# Foc_Power.net
KiCad netlist of a schematic drawn in Altium Designer
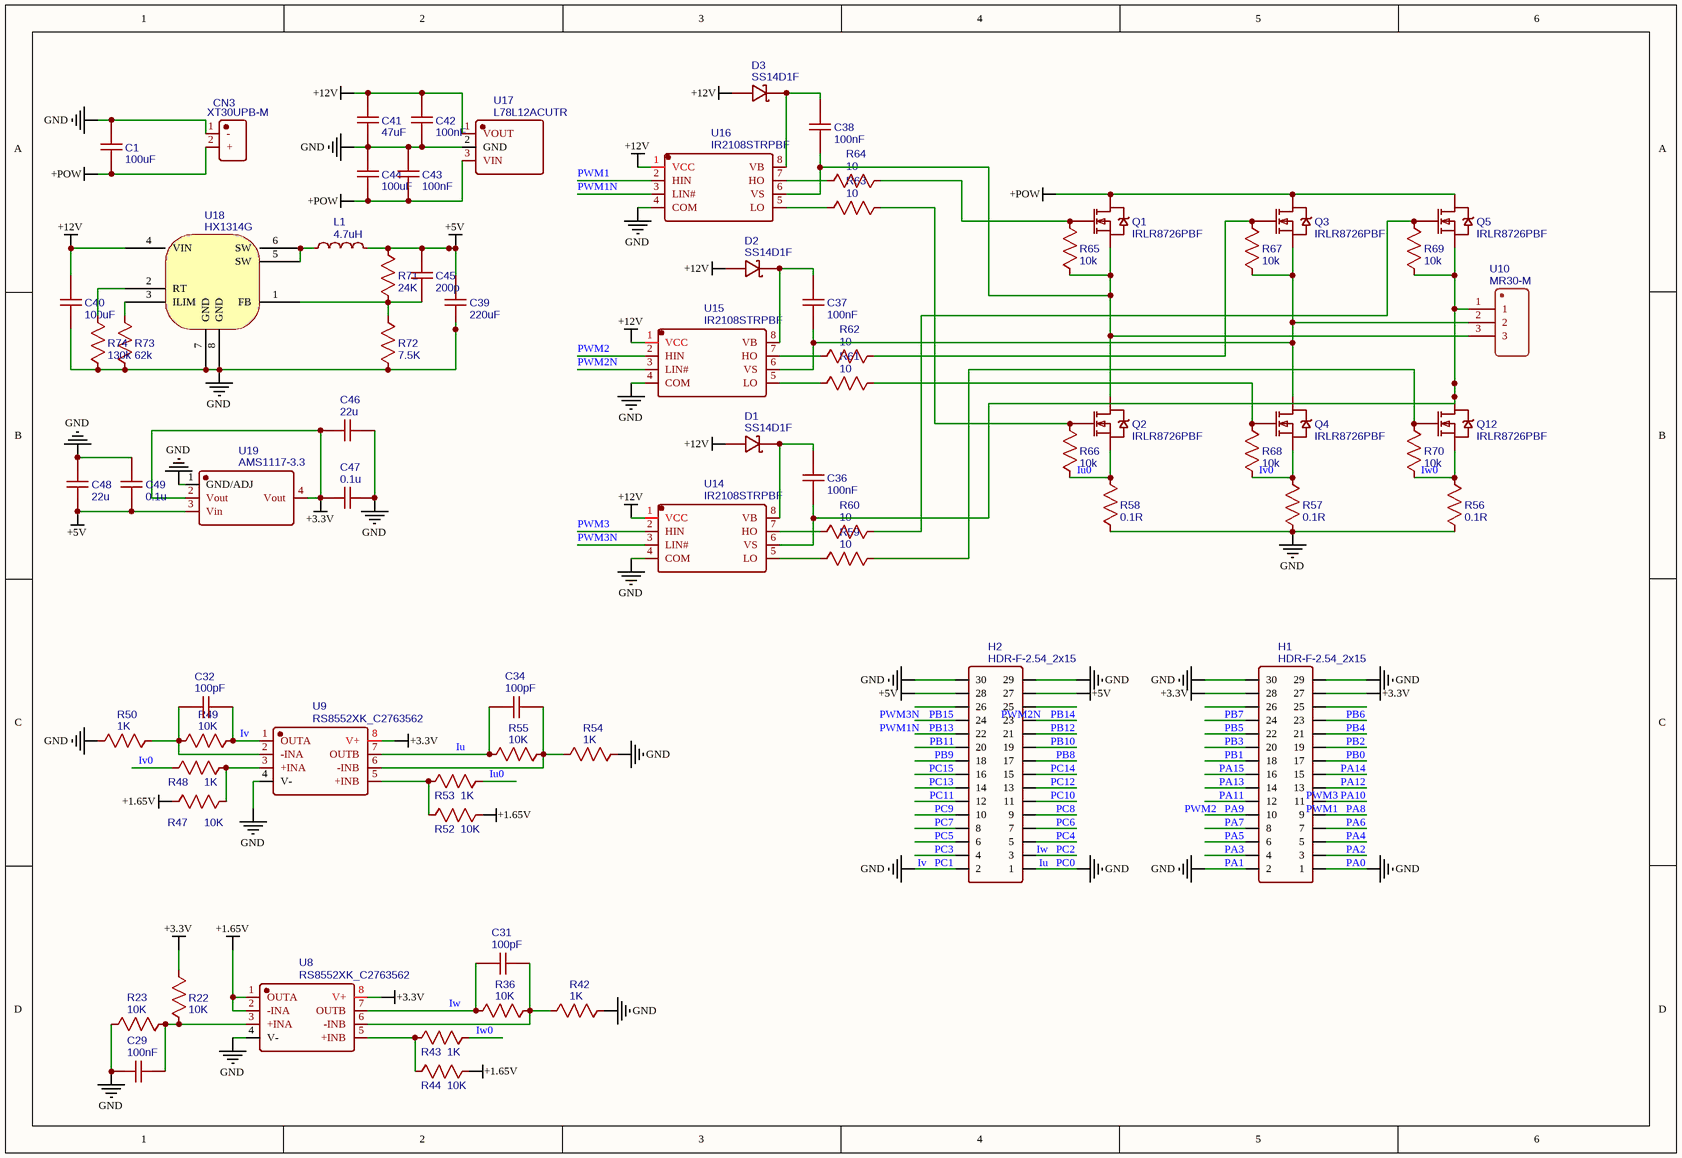
[diagram p0: Foc_Power.schdoc]

(export (version "E")
  (design (tool "Eeschema 10.0.6"))
  (components
    (comp (ref "C1")
      (value "100uF")
      (footprint "C1206")
      (fields (field (name "CONTRIBUTOR") "LCEDA_Lib"))
      (libsource (lib "altium-import") (part "root_1_100uF_"))
    )
    (comp (ref "C29")
      (value "100nF")
      (footprint "C0603")
      (fields (field (name "CONTRIBUTOR") "LCEDA_Lib"))
      (libsource (lib "altium-import") (part "root_2_100nF_"))
    )
    (comp (ref "C31")
      (value "100pF")
      (footprint "C0603")
      (fields (field (name "CONTRIBUTOR") "LCEDA_Lib"))
      (libsource (lib "altium-import") (part "root_2_100pF_"))
    )
    (comp (ref "C32")
      (value "100pF")
      (footprint "C0603")
      (fields (field (name "CONTRIBUTOR") "LCEDA_Lib"))
      (libsource (lib "altium-import") (part "root_2_100pF_"))
    )
    (comp (ref "C34")
      (value "100pF")
      (footprint "C0603")
      (fields (field (name "CONTRIBUTOR") "LCEDA_Lib"))
      (libsource (lib "altium-import") (part "root_2_100pF_"))
    )
    (comp (ref "C36")
      (value "100nF")
      (footprint "C0603")
      (fields (field (name "CONTRIBUTOR") "LCEDA_Lib"))
      (libsource (lib "altium-import") (part "root_1_100nF_"))
    )
    (comp (ref "C37")
      (value "100nF")
      (footprint "C0603")
      (fields (field (name "CONTRIBUTOR") "LCEDA_Lib"))
      (libsource (lib "altium-import") (part "root_1_100nF_"))
    )
    (comp (ref "C38")
      (value "100nF")
      (footprint "C0603")
      (fields (field (name "CONTRIBUTOR") "LCEDA_Lib"))
      (libsource (lib "altium-import") (part "root_1_100nF_"))
    )
    (comp (ref "C39")
      (value "220uF")
      (footprint "C1206")
      (fields (field (name "CONTRIBUTOR") "LCEDA_Lib"))
      (libsource (lib "altium-import") (part "root_1_220uF_"))
    )
    (comp (ref "C40")
      (value "100uF")
      (footprint "C1206")
      (fields (field (name "CONTRIBUTOR") "LCEDA_Lib"))
      (libsource (lib "altium-import") (part "root_1_100uF_"))
    )
    (comp (ref "C41")
      (value "47uF")
      (footprint "C1206")
      (fields (field (name "CONTRIBUTOR") "LCEDA_Lib"))
      (libsource (lib "altium-import") (part "root_1_47uF_"))
    )
    (comp (ref "C42")
      (value "100nF")
      (footprint "C1206")
      (fields (field (name "CONTRIBUTOR") "LCEDA_Lib"))
      (libsource (lib "altium-import") (part "root_1_100nF_"))
    )
    (comp (ref "C43")
      (value "100nF")
      (footprint "C1206")
      (fields (field (name "CONTRIBUTOR") "LCEDA_Lib"))
      (libsource (lib "altium-import") (part "root_1_100nF_"))
    )
    (comp (ref "C44")
      (value "100uF")
      (footprint "C1206")
      (fields (field (name "CONTRIBUTOR") "LCEDA_Lib"))
      (libsource (lib "altium-import") (part "root_1_100uF_"))
    )
    (comp (ref "C45")
      (value "200p")
      (footprint "C0603")
      (fields (field (name "CONTRIBUTOR") "LCEDA_Lib"))
      (libsource (lib "altium-import") (part "root_1_200p_"))
    )
    (comp (ref "C46")
      (value "22u")
      (footprint "C0603")
      (fields (field (name "CONTRIBUTOR") "LCEDA_Lib"))
      (libsource (lib "altium-import") (part "root_0_22u_"))
    )
    (comp (ref "C47")
      (value "0.1u")
      (footprint "C0603")
      (fields (field (name "CONTRIBUTOR") "LCEDA_Lib"))
      (libsource (lib "altium-import") (part "root_0_0.1u_"))
    )
    (comp (ref "C48")
      (value "22u")
      (footprint "C0603")
      (fields (field (name "CONTRIBUTOR") "LCEDA_Lib"))
      (libsource (lib "altium-import") (part "root_1_22u_"))
    )
    (comp (ref "C49")
      (value "0.1u")
      (footprint "C0603")
      (fields (field (name "CONTRIBUTOR") "LCEDA_Lib"))
      (libsource (lib "altium-import") (part "root_1_0.1u_"))
    )
    (comp (ref "CN3")
      (value "XT30UPB-M")
      (footprint "CONN-TH_XT30UPB-M")
      (fields (field (name "BOM_SUPPLIER PART") "C428721") (field (name "CONTRIBUTOR") "LCSC"))
      (libsource (lib "altium-import") (part "root_0_XT30UPB-M_"))
    )
    (comp (ref "D1")
      (value "SS14D1F")
      (footprint "SOD-123_L2.8-W1.8-LS3.7-RD")
      (fields (field (name "BOM_SUPPLIER PART") "C555467") (field (name "CONTRIBUTOR") "LCSC"))
      (libsource (lib "altium-import") (part "root_2_SS14D1F_"))
    )
    (comp (ref "D2")
      (value "SS14D1F")
      (footprint "SOD-123_L2.8-W1.8-LS3.7-RD")
      (fields (field (name "BOM_SUPPLIER PART") "C555467") (field (name "CONTRIBUTOR") "LCSC"))
      (libsource (lib "altium-import") (part "root_2_SS14D1F_"))
    )
    (comp (ref "D3")
      (value "SS14D1F")
      (footprint "SOD-123_L2.8-W1.8-LS3.7-RD")
      (fields (field (name "BOM_SUPPLIER PART") "C555467") (field (name "CONTRIBUTOR") "LCSC"))
      (libsource (lib "altium-import") (part "root_2_SS14D1F_"))
    )
    (comp (ref "H1")
      (value "HDR-F-2.54_2x15")
      (footprint "HDR-F-2.54_2X15")
      (fields (field (name "BOM_SUPPLIER PART") "C169818") (field (name "CONTRIBUTOR") "LCEDA_Lib"))
      (libsource (lib "altium-import") (part "root_2_HDR-F-2.54_2x15_"))
    )
    (comp (ref "H2")
      (value "HDR-F-2.54_2x15")
      (footprint "HDR-F-2.54_2X15")
      (fields (field (name "BOM_SUPPLIER PART") "C169818") (field (name "CONTRIBUTOR") "LCEDA_Lib"))
      (libsource (lib "altium-import") (part "root_2_HDR-F-2.54_2x15_"))
    )
    (comp (ref "L1")
      (value "4.7uH")
      (footprint "L0805")
      (fields (field (name "CONTRIBUTOR") "LCEDA_Lib"))
      (libsource (lib "altium-import") (part "root_0_4.7uH_"))
    )
    (comp (ref "Q1")
      (value "IRLR8726PBF")
      (footprint "TO-252-2_L6.6-W6.1-P4.57-LS9.9-BR-CW")
      (fields (field (name "BOM_SUPPLIER PART") "C110317"))
      (libsource (lib "altium-import") (part "root_0_IRLR8726PBF_"))
    )
    (comp (ref "Q2")
      (value "IRLR8726PBF")
      (footprint "TO-252-2_L6.6-W6.1-P4.57-LS9.9-BR-CW")
      (fields (field (name "BOM_SUPPLIER PART") "C110317"))
      (libsource (lib "altium-import") (part "root_0_IRLR8726PBF_"))
    )
    (comp (ref "Q3")
      (value "IRLR8726PBF")
      (footprint "TO-252-2_L6.6-W6.1-P4.57-LS9.9-BR-CW")
      (fields (field (name "BOM_SUPPLIER PART") "C110317"))
      (libsource (lib "altium-import") (part "root_0_IRLR8726PBF_"))
    )
    (comp (ref "Q4")
      (value "IRLR8726PBF")
      (footprint "TO-252-2_L6.6-W6.1-P4.57-LS9.9-BR-CW")
      (fields (field (name "BOM_SUPPLIER PART") "C110317"))
      (libsource (lib "altium-import") (part "root_0_IRLR8726PBF_"))
    )
    (comp (ref "Q5")
      (value "IRLR8726PBF")
      (footprint "TO-252-2_L6.6-W6.1-P4.57-LS9.9-BR-CW")
      (fields (field (name "BOM_SUPPLIER PART") "C110317"))
      (libsource (lib "altium-import") (part "root_0_IRLR8726PBF_"))
    )
    (comp (ref "Q12")
      (value "IRLR8726PBF")
      (footprint "TO-252-2_L6.6-W6.1-P4.57-LS9.9-BR-CW")
      (fields (field (name "BOM_SUPPLIER PART") "C110317"))
      (libsource (lib "altium-import") (part "root_0_IRLR8726PBF_"))
    )
    (comp (ref "R22")
      (value "10K")
      (footprint "R0603")
      (fields (field (name "CONTRIBUTOR") "LCEDA_Lib"))
      (libsource (lib "altium-import") (part "root_3_10K_"))
    )
    (comp (ref "R23")
      (value "10K")
      (footprint "R0603")
      (fields (field (name "CONTRIBUTOR") "LCEDA_Lib"))
      (libsource (lib "altium-import") (part "root_2_10K_"))
    )
    (comp (ref "R36")
      (value "10K")
      (footprint "R0603")
      (fields (field (name "CONTRIBUTOR") "LCEDA_Lib"))
      (libsource (lib "altium-import") (part "root_0_10K_"))
    )
    (comp (ref "R42")
      (value "1K")
      (footprint "R0603")
      (fields (field (name "CONTRIBUTOR") "LCEDA_Lib"))
      (libsource (lib "altium-import") (part "root_0_1K_"))
    )
    (comp (ref "R43")
      (value "1K")
      (footprint "R0603")
      (fields (field (name "CONTRIBUTOR") "LCEDA_Lib"))
      (libsource (lib "altium-import") (part "root_0_1K_"))
    )
    (comp (ref "R44")
      (value "10K")
      (footprint "R0603")
      (fields (field (name "CONTRIBUTOR") "LCEDA_Lib"))
      (libsource (lib "altium-import") (part "root_0_10K_"))
    )
    (comp (ref "R47")
      (value "10K")
      (footprint "R0603")
      (fields (field (name "CONTRIBUTOR") "LCEDA_Lib"))
      (libsource (lib "altium-import") (part "root_0_10K_"))
    )
    (comp (ref "R48")
      (value "1K")
      (footprint "R0603")
      (fields (field (name "CONTRIBUTOR") "LCEDA_Lib"))
      (libsource (lib "altium-import") (part "root_0_1K_"))
    )
    (comp (ref "R49")
      (value "10K")
      (footprint "R0603")
      (fields (field (name "CONTRIBUTOR") "LCEDA_Lib"))
      (libsource (lib "altium-import") (part "root_0_10K_"))
    )
    (comp (ref "R50")
      (value "1K")
      (footprint "R0603")
      (fields (field (name "CONTRIBUTOR") "LCEDA_Lib"))
      (libsource (lib "altium-import") (part "root_0_1K_"))
    )
    (comp (ref "R52")
      (value "10K")
      (footprint "R0603")
      (fields (field (name "CONTRIBUTOR") "LCEDA_Lib"))
      (libsource (lib "altium-import") (part "root_0_10K_"))
    )
    (comp (ref "R53")
      (value "1K")
      (footprint "R0603")
      (fields (field (name "CONTRIBUTOR") "LCEDA_Lib"))
      (libsource (lib "altium-import") (part "root_0_1K_"))
    )
    (comp (ref "R54")
      (value "1K")
      (footprint "R0603")
      (fields (field (name "CONTRIBUTOR") "LCEDA_Lib"))
      (libsource (lib "altium-import") (part "root_0_1K_"))
    )
    (comp (ref "R55")
      (value "10K")
      (footprint "R0603")
      (fields (field (name "CONTRIBUTOR") "LCEDA_Lib"))
      (libsource (lib "altium-import") (part "root_0_10K_"))
    )
    (comp (ref "R56")
      (value "0.1R")
      (footprint "R1206")
      (fields (field (name "CONTRIBUTOR") "LCEDA_Lib"))
      (libsource (lib "altium-import") (part "root_1_0.1R_"))
    )
    (comp (ref "R57")
      (value "0.1R")
      (footprint "R1206")
      (fields (field (name "CONTRIBUTOR") "LCEDA_Lib"))
      (libsource (lib "altium-import") (part "root_1_0.1R_"))
    )
    (comp (ref "R58")
      (value "0.1R")
      (footprint "R1206")
      (fields (field (name "CONTRIBUTOR") "LCEDA_Lib"))
      (libsource (lib "altium-import") (part "root_1_0.1R_"))
    )
    (comp (ref "R59")
      (value "10")
      (footprint "R0603")
      (fields (field (name "CONTRIBUTOR") "LCEDA_Lib"))
      (libsource (lib "altium-import") (part "root_0_10_"))
    )
    (comp (ref "R60")
      (value "10")
      (footprint "R0603")
      (fields (field (name "CONTRIBUTOR") "LCEDA_Lib"))
      (libsource (lib "altium-import") (part "root_0_10_"))
    )
    (comp (ref "R61")
      (value "10")
      (footprint "R0603")
      (fields (field (name "CONTRIBUTOR") "LCEDA_Lib"))
      (libsource (lib "altium-import") (part "root_0_10_"))
    )
    (comp (ref "R62")
      (value "10")
      (footprint "R0603")
      (fields (field (name "CONTRIBUTOR") "LCEDA_Lib"))
      (libsource (lib "altium-import") (part "root_0_10_"))
    )
    (comp (ref "R63")
      (value "10")
      (footprint "R0603")
      (fields (field (name "CONTRIBUTOR") "LCEDA_Lib"))
      (libsource (lib "altium-import") (part "root_0_10_"))
    )
    (comp (ref "R64")
      (value "10")
      (footprint "R0603")
      (fields (field (name "CONTRIBUTOR") "LCEDA_Lib"))
      (libsource (lib "altium-import") (part "root_0_10_"))
    )
    (comp (ref "R65")
      (value "10k")
      (footprint "R0603")
      (fields (field (name "CONTRIBUTOR") "LCEDA_Lib"))
      (libsource (lib "altium-import") (part "root_1_10k_"))
    )
    (comp (ref "R66")
      (value "10k")
      (footprint "R0603")
      (fields (field (name "CONTRIBUTOR") "LCEDA_Lib"))
      (libsource (lib "altium-import") (part "root_1_10k_"))
    )
    (comp (ref "R67")
      (value "10k")
      (footprint "R0603")
      (fields (field (name "CONTRIBUTOR") "LCEDA_Lib"))
      (libsource (lib "altium-import") (part "root_1_10k_"))
    )
    (comp (ref "R68")
      (value "10k")
      (footprint "R0603")
      (fields (field (name "CONTRIBUTOR") "LCEDA_Lib"))
      (libsource (lib "altium-import") (part "root_1_10k_"))
    )
    (comp (ref "R69")
      (value "10k")
      (footprint "R0603")
      (fields (field (name "CONTRIBUTOR") "LCEDA_Lib"))
      (libsource (lib "altium-import") (part "root_1_10k_"))
    )
    (comp (ref "R70")
      (value "10k")
      (footprint "R0603")
      (fields (field (name "CONTRIBUTOR") "LCEDA_Lib"))
      (libsource (lib "altium-import") (part "root_1_10k_"))
    )
    (comp (ref "R71")
      (value "24K")
      (footprint "R0603")
      (fields (field (name "CONTRIBUTOR") "LCEDA_Lib"))
      (libsource (lib "altium-import") (part "root_1_24K_"))
    )
    (comp (ref "R72")
      (value "7.5K")
      (footprint "R0603")
      (fields (field (name "CONTRIBUTOR") "LCEDA_Lib"))
      (libsource (lib "altium-import") (part "root_1_7.5K_"))
    )
    (comp (ref "R73")
      (value "62k")
      (footprint "R0603")
      (fields (field (name "CONTRIBUTOR") "LCEDA_Lib"))
      (libsource (lib "altium-import") (part "root_1_62k_"))
    )
    (comp (ref "R74")
      (value "130k")
      (footprint "R0603")
      (fields (field (name "CONTRIBUTOR") "LCEDA_Lib"))
      (libsource (lib "altium-import") (part "root_1_130k_"))
    )
    (comp (ref "U8")
      (value "RS8552XK_C2763562")
      (footprint "SOIC-8_L4.9-W3.9-P1.27-LS6.0-BL")
      (fields
        (field (name "BOM_SUPPLIER PART") "C2763562")
        (field (name "BOM_MANUFACTURER PART") "RS8552XK")
        (field (name "CONTRIBUTOR") "LCSC")
      )
      (libsource (lib "altium-import") (part "root_0_RS8552XK_C2763562_"))
    )
    (comp (ref "U9")
      (value "RS8552XK_C2763562")
      (footprint "SOIC-8_L4.9-W3.9-P1.27-LS6.0-BL")
      (fields
        (field (name "BOM_SUPPLIER PART") "C2763562")
        (field (name "BOM_MANUFACTURER PART") "RS8552XK")
        (field (name "CONTRIBUTOR") "LCSC")
      )
      (libsource (lib "altium-import") (part "root_0_RS8552XK_C2763562_"))
    )
    (comp (ref "U10")
      (value "MR30-M")
      (footprint "MR30-M")
      (fields (field (name "CONTRIBUTOR") "杜邦线丶小战士"))
      (libsource (lib "altium-import") (part "root_0_MR30-M_"))
    )
    (comp (ref "U14")
      (value "IR2108STRPBF")
      (footprint "SOIC-8_L4.9-W3.9-P1.27-LS6.0-BL")
      (fields (field (name "BOM_SUPPLIER PART") "C2964"))
      (libsource (lib "altium-import") (part "root_0_IR2108STRPBF_"))
    )
    (comp (ref "U15")
      (value "IR2108STRPBF")
      (footprint "SOIC-8_L4.9-W3.9-P1.27-LS6.0-BL")
      (fields (field (name "BOM_SUPPLIER PART") "C2964"))
      (libsource (lib "altium-import") (part "root_0_IR2108STRPBF_"))
    )
    (comp (ref "U16")
      (value "IR2108STRPBF")
      (footprint "SOIC-8_L4.9-W3.9-P1.27-LS6.0-BL")
      (fields (field (name "BOM_SUPPLIER PART") "C2964"))
      (libsource (lib "altium-import") (part "root_0_IR2108STRPBF_"))
    )
    (comp (ref "U17")
      (value "L78L12ACUTR")
      (footprint "SOT-89-3_L4.5-W2.5-P1.50-LS4.2-TL")
      (fields (field (name "BOM_SUPPLIER PART") "C69601") (field (name "CONTRIBUTOR") "LCSC"))
      (libsource (lib "altium-import") (part "root_0_L78L12ACUTR_"))
    )
    (comp (ref "U18")
      (value "HX1314G")
      (footprint "SOP8")
      (fields (field (name "CONTRIBUTOR") "lzhfz_0591"))
      (libsource (lib "altium-import") (part "root_0_HX1314G_"))
    )
    (comp (ref "U19")
      (value "AMS1117-3.3")
      (footprint "SOT-223-3_L6.5-W3.4-P2.30-LS7.0-BR")
      (fields (field (name "BOM_SUPPLIER PART") "C6186"))
      (libsource (lib "altium-import") (part "root_0_AMS1117-3.3_"))
    )
  )
  (nets
    (net (code "1") (name "+1.65V") (class "Default")
      (node (ref "R44") (pin "2") (pinfunction "2_2") (pintype "passive"))
      (node (ref "R47") (pin "1") (pinfunction "1_1") (pintype "passive"))
      (node (ref "R52") (pin "2") (pinfunction "2_2") (pintype "passive"))
      (node (ref "U8") (pin "1") (pinfunction "OUTA_1") (pintype "passive"))
      (node (ref "U8") (pin "2") (pinfunction "-INA_2") (pintype "passive"))
    )
    (net (code "2") (name "+3.3V") (class "Default")
      (node (ref "C46") (pin "1") (pinfunction "1_1") (pintype "passive"))
      (node (ref "C47") (pin "1") (pinfunction "1_1") (pintype "passive"))
      (node (ref "H1") (pin "27") (pinfunction "27_27") (pintype "passive"))
      (node (ref "H1") (pin "28") (pinfunction "28_28") (pintype "passive"))
      (node (ref "R22") (pin "1") (pinfunction "1_1") (pintype "passive"))
      (node (ref "U19") (pin "2") (pinfunction "Vout_2") (pintype "passive"))
      (node (ref "U19") (pin "4") (pinfunction "Vout_4") (pintype "passive"))
      (node (ref "U8") (pin "8") (pinfunction "V+_8") (pintype "passive"))
      (node (ref "U9") (pin "8") (pinfunction "V+_8") (pintype "passive"))
    )
    (net (code "3") (name "+5V") (class "Default")
      (node (ref "C39") (pin "2") (pinfunction "2_2") (pintype "passive"))
      (node (ref "C45") (pin "2") (pinfunction "2_2") (pintype "passive"))
      (node (ref "C48") (pin "1") (pinfunction "1_1") (pintype "passive"))
      (node (ref "C49") (pin "1") (pinfunction "1_1") (pintype "passive"))
      (node (ref "H2") (pin "27") (pinfunction "27_27") (pintype "passive"))
      (node (ref "H2") (pin "28") (pinfunction "28_28") (pintype "passive"))
      (node (ref "L1") (pin "2") (pinfunction "2_2") (pintype "passive"))
      (node (ref "R71") (pin "2") (pinfunction "2_2") (pintype "passive"))
      (node (ref "U19") (pin "3") (pinfunction "Vin_3") (pintype "passive"))
    )
    (net (code "4") (name "+12V") (class "Default")
      (node (ref "C40") (pin "2") (pinfunction "2_2") (pintype "passive"))
      (node (ref "C41") (pin "2") (pinfunction "2_2") (pintype "passive"))
      (node (ref "C42") (pin "2") (pinfunction "2_2") (pintype "passive"))
      (node (ref "D1") (pin "2") (pinfunction "2_2") (pintype "passive"))
      (node (ref "D2") (pin "2") (pinfunction "2_2") (pintype "passive"))
      (node (ref "D3") (pin "2") (pinfunction "2_2") (pintype "passive"))
      (node (ref "U14") (pin "1") (pinfunction "VCC_1") (pintype "passive"))
      (node (ref "U15") (pin "1") (pinfunction "VCC_1") (pintype "passive"))
      (node (ref "U16") (pin "1") (pinfunction "VCC_1") (pintype "passive"))
      (node (ref "U17") (pin "1") (pinfunction "VOUT_1") (pintype "passive"))
      (node (ref "U18") (pin "4") (pinfunction "VIN_4") (pintype "passive"))
    )
    (net (code "5") (name "+POW") (class "Default")
      (node (ref "C1") (pin "1") (pinfunction "1_1") (pintype "passive"))
      (node (ref "C43") (pin "1") (pinfunction "1_1") (pintype "passive"))
      (node (ref "C44") (pin "1") (pinfunction "1_1") (pintype "passive"))
      (node (ref "CN3") (pin "2") (pinfunction "+_2") (pintype "passive"))
      (node (ref "Q1") (pin "2") (pinfunction "D_2") (pintype "passive"))
      (node (ref "Q3") (pin "2") (pinfunction "D_2") (pintype "passive"))
      (node (ref "Q5") (pin "2") (pinfunction "D_2") (pintype "passive"))
      (node (ref "U17") (pin "3") (pinfunction "VIN_3") (pintype "passive"))
    )
    (net (code "6") (name "/Iu") (class "Default")
      (node (ref "C34") (pin "2") (pinfunction "2_2") (pintype "passive"))
      (node (ref "H2") (pin "3") (pinfunction "3_3") (pintype "passive"))
      (node (ref "R55") (pin "1") (pinfunction "1_1") (pintype "passive"))
      (node (ref "U9") (pin "7") (pinfunction "OUTB_7") (pintype "passive"))
    )
    (net (code "7") (name "/Iu0") (class "Default")
      (node (ref "Q2") (pin "3") (pinfunction "S_3") (pintype "passive"))
      (node (ref "R53") (pin "2") (pinfunction "2_2") (pintype "passive"))
      (node (ref "R58") (pin "2") (pinfunction "2_2") (pintype "passive"))
      (node (ref "R66") (pin "1") (pinfunction "1_1") (pintype "passive"))
    )
    (net (code "8") (name "/Iv") (class "Default")
      (node (ref "C32") (pin "1") (pinfunction "1_1") (pintype "passive"))
      (node (ref "H2") (pin "4") (pinfunction "4_4") (pintype "passive"))
      (node (ref "R49") (pin "2") (pinfunction "2_2") (pintype "passive"))
      (node (ref "U9") (pin "1") (pinfunction "OUTA_1") (pintype "passive"))
    )
    (net (code "9") (name "/Iv0") (class "Default")
      (node (ref "Q4") (pin "3") (pinfunction "S_3") (pintype "passive"))
      (node (ref "R48") (pin "1") (pinfunction "1_1") (pintype "passive"))
      (node (ref "R57") (pin "2") (pinfunction "2_2") (pintype "passive"))
      (node (ref "R68") (pin "1") (pinfunction "1_1") (pintype "passive"))
    )
    (net (code "10") (name "/Iw") (class "Default")
      (node (ref "C31") (pin "2") (pinfunction "2_2") (pintype "passive"))
      (node (ref "H2") (pin "5") (pinfunction "5_5") (pintype "passive"))
      (node (ref "R36") (pin "1") (pinfunction "1_1") (pintype "passive"))
      (node (ref "U8") (pin "7") (pinfunction "OUTB_7") (pintype "passive"))
    )
    (net (code "11") (name "/Iw0") (class "Default")
      (node (ref "Q12") (pin "3") (pinfunction "S_3") (pintype "passive"))
      (node (ref "R43") (pin "2") (pinfunction "2_2") (pintype "passive"))
      (node (ref "R56") (pin "2") (pinfunction "2_2") (pintype "passive"))
      (node (ref "R70") (pin "1") (pinfunction "1_1") (pintype "passive"))
    )
    (net (code "12") (name "/PA0") (class "Default")
      (node (ref "H1") (pin "3") (pinfunction "3_3") (pintype "passive"))
    )
    (net (code "13") (name "/PA1") (class "Default")
      (node (ref "H1") (pin "4") (pinfunction "4_4") (pintype "passive"))
    )
    (net (code "14") (name "/PA2") (class "Default")
      (node (ref "H1") (pin "5") (pinfunction "5_5") (pintype "passive"))
    )
    (net (code "15") (name "/PA3") (class "Default")
      (node (ref "H1") (pin "6") (pinfunction "6_6") (pintype "passive"))
    )
    (net (code "16") (name "/PA4") (class "Default")
      (node (ref "H1") (pin "7") (pinfunction "7_7") (pintype "passive"))
    )
    (net (code "17") (name "/PA5") (class "Default")
      (node (ref "H1") (pin "8") (pinfunction "8_8") (pintype "passive"))
    )
    (net (code "18") (name "/PA6") (class "Default")
      (node (ref "H1") (pin "9") (pinfunction "9_9") (pintype "passive"))
    )
    (net (code "19") (name "/PA7") (class "Default")
      (node (ref "H1") (pin "10") (pinfunction "10_10") (pintype "passive"))
    )
    (net (code "20") (name "/PA8") (class "Default")
      (node (ref "H1") (pin "11") (pinfunction "11_11") (pintype "passive"))
      (node (ref "U16") (pin "2") (pinfunction "HIN_2") (pintype "passive"))
    )
    (net (code "21") (name "/PA9") (class "Default")
      (node (ref "H1") (pin "12") (pinfunction "12_12") (pintype "passive"))
      (node (ref "U15") (pin "2") (pinfunction "HIN_2") (pintype "passive"))
    )
    (net (code "22") (name "/PA10") (class "Default")
      (node (ref "H1") (pin "13") (pinfunction "13_13") (pintype "passive"))
      (node (ref "U14") (pin "2") (pinfunction "HIN_2") (pintype "passive"))
    )
    (net (code "23") (name "/PA11") (class "Default")
      (node (ref "H1") (pin "14") (pinfunction "14_14") (pintype "passive"))
    )
    (net (code "24") (name "/PA12") (class "Default")
      (node (ref "H1") (pin "15") (pinfunction "15_15") (pintype "passive"))
    )
    (net (code "25") (name "/PA13") (class "Default")
      (node (ref "H1") (pin "16") (pinfunction "16_16") (pintype "passive"))
    )
    (net (code "26") (name "/PA14") (class "Default")
      (node (ref "H1") (pin "17") (pinfunction "17_17") (pintype "passive"))
    )
    (net (code "27") (name "/PA15") (class "Default")
      (node (ref "H1") (pin "18") (pinfunction "18_18") (pintype "passive"))
    )
    (net (code "28") (name "/PB0") (class "Default")
      (node (ref "H1") (pin "19") (pinfunction "19_19") (pintype "passive"))
    )
    (net (code "29") (name "/PB1") (class "Default")
      (node (ref "H1") (pin "20") (pinfunction "20_20") (pintype "passive"))
    )
    (net (code "30") (name "/PB2") (class "Default")
      (node (ref "H1") (pin "21") (pinfunction "21_21") (pintype "passive"))
    )
    (net (code "31") (name "/PB3") (class "Default")
      (node (ref "H1") (pin "22") (pinfunction "22_22") (pintype "passive"))
    )
    (net (code "32") (name "/PB4") (class "Default")
      (node (ref "H1") (pin "23") (pinfunction "23_23") (pintype "passive"))
    )
    (net (code "33") (name "/PB5") (class "Default")
      (node (ref "H1") (pin "24") (pinfunction "24_24") (pintype "passive"))
    )
    (net (code "34") (name "/PB6") (class "Default")
      (node (ref "H1") (pin "25") (pinfunction "25_25") (pintype "passive"))
    )
    (net (code "35") (name "/PB7") (class "Default")
      (node (ref "H1") (pin "26") (pinfunction "26_26") (pintype "passive"))
    )
    (net (code "36") (name "/PB8") (class "Default")
      (node (ref "H2") (pin "19") (pinfunction "19_19") (pintype "passive"))
    )
    (net (code "37") (name "/PB9") (class "Default")
      (node (ref "H2") (pin "20") (pinfunction "20_20") (pintype "passive"))
    )
    (net (code "38") (name "/PB10") (class "Default")
      (node (ref "H2") (pin "21") (pinfunction "21_21") (pintype "passive"))
    )
    (net (code "39") (name "/PB11") (class "Default")
      (node (ref "H2") (pin "22") (pinfunction "22_22") (pintype "passive"))
    )
    (net (code "40") (name "/PB12") (class "Default")
      (node (ref "H2") (pin "23") (pinfunction "23_23") (pintype "passive"))
    )
    (net (code "41") (name "/PB13") (class "Default")
      (node (ref "H2") (pin "24") (pinfunction "24_24") (pintype "passive"))
      (node (ref "U16") (pin "3") (pinfunction "LIN#_3") (pintype "passive"))
    )
    (net (code "42") (name "/PB14") (class "Default")
      (node (ref "H2") (pin "25") (pinfunction "25_25") (pintype "passive"))
      (node (ref "U15") (pin "3") (pinfunction "LIN#_3") (pintype "passive"))
    )
    (net (code "43") (name "/PB15") (class "Default")
      (node (ref "H2") (pin "26") (pinfunction "26_26") (pintype "passive"))
      (node (ref "U14") (pin "3") (pinfunction "LIN#_3") (pintype "passive"))
    )
    (net (code "44") (name "/PC3") (class "Default")
      (node (ref "H2") (pin "6") (pinfunction "6_6") (pintype "passive"))
    )
    (net (code "45") (name "/PC4") (class "Default")
      (node (ref "H2") (pin "7") (pinfunction "7_7") (pintype "passive"))
    )
    (net (code "46") (name "/PC5") (class "Default")
      (node (ref "H2") (pin "8") (pinfunction "8_8") (pintype "passive"))
    )
    (net (code "47") (name "/PC6") (class "Default")
      (node (ref "H2") (pin "9") (pinfunction "9_9") (pintype "passive"))
    )
    (net (code "48") (name "/PC7") (class "Default")
      (node (ref "H2") (pin "10") (pinfunction "10_10") (pintype "passive"))
    )
    (net (code "49") (name "/PC8") (class "Default")
      (node (ref "H2") (pin "11") (pinfunction "11_11") (pintype "passive"))
    )
    (net (code "50") (name "/PC9") (class "Default")
      (node (ref "H2") (pin "12") (pinfunction "12_12") (pintype "passive"))
    )
    (net (code "51") (name "/PC10") (class "Default")
      (node (ref "H2") (pin "13") (pinfunction "13_13") (pintype "passive"))
    )
    (net (code "52") (name "/PC11") (class "Default")
      (node (ref "H2") (pin "14") (pinfunction "14_14") (pintype "passive"))
    )
    (net (code "53") (name "/PC12") (class "Default")
      (node (ref "H2") (pin "15") (pinfunction "15_15") (pintype "passive"))
    )
    (net (code "54") (name "/PC13") (class "Default")
      (node (ref "H2") (pin "16") (pinfunction "16_16") (pintype "passive"))
    )
    (net (code "55") (name "/PC14") (class "Default")
      (node (ref "H2") (pin "17") (pinfunction "17_17") (pintype "passive"))
    )
    (net (code "56") (name "/PC15") (class "Default")
      (node (ref "H2") (pin "18") (pinfunction "18_18") (pintype "passive"))
    )
    (net (code "57") (name "GND") (class "Default")
      (node (ref "C1") (pin "2") (pinfunction "2_2") (pintype "passive"))
      (node (ref "C29") (pin "2") (pinfunction "2_2") (pintype "passive"))
      (node (ref "C39") (pin "1") (pinfunction "1_1") (pintype "passive"))
      (node (ref "C40") (pin "1") (pinfunction "1_1") (pintype "passive"))
      (node (ref "C41") (pin "1") (pinfunction "1_1") (pintype "passive"))
      (node (ref "C42") (pin "1") (pinfunction "1_1") (pintype "passive"))
      (node (ref "C43") (pin "2") (pinfunction "2_2") (pintype "passive"))
      (node (ref "C44") (pin "2") (pinfunction "2_2") (pintype "passive"))
      (node (ref "C46") (pin "2") (pinfunction "2_2") (pintype "passive"))
      (node (ref "C47") (pin "2") (pinfunction "2_2") (pintype "passive"))
      (node (ref "C48") (pin "2") (pinfunction "2_2") (pintype "passive"))
      (node (ref "C49") (pin "2") (pinfunction "2_2") (pintype "passive"))
      (node (ref "CN3") (pin "1") (pinfunction "-_1") (pintype "passive"))
      (node (ref "H1") (pin "1") (pinfunction "1_1") (pintype "passive"))
      (node (ref "H1") (pin "2") (pinfunction "2_2") (pintype "passive"))
      (node (ref "H1") (pin "29") (pinfunction "29_29") (pintype "passive"))
      (node (ref "H1") (pin "30") (pinfunction "30_30") (pintype "passive"))
      (node (ref "H2") (pin "1") (pinfunction "1_1") (pintype "passive"))
      (node (ref "H2") (pin "2") (pinfunction "2_2") (pintype "passive"))
      (node (ref "H2") (pin "29") (pinfunction "29_29") (pintype "passive"))
      (node (ref "H2") (pin "30") (pinfunction "30_30") (pintype "passive"))
      (node (ref "R23") (pin "2") (pinfunction "2_2") (pintype "passive"))
      (node (ref "R42") (pin "2") (pinfunction "2_2") (pintype "passive"))
      (node (ref "R50") (pin "1") (pinfunction "1_1") (pintype "passive"))
      (node (ref "R54") (pin "2") (pinfunction "2_2") (pintype "passive"))
      (node (ref "R56") (pin "1") (pinfunction "1_1") (pintype "passive"))
      (node (ref "R57") (pin "1") (pinfunction "1_1") (pintype "passive"))
      (node (ref "R58") (pin "1") (pinfunction "1_1") (pintype "passive"))
      (node (ref "R72") (pin "1") (pinfunction "1_1") (pintype "passive"))
      (node (ref "R73") (pin "1") (pinfunction "1_1") (pintype "passive"))
      (node (ref "R74") (pin "1") (pinfunction "1_1") (pintype "passive"))
      (node (ref "U14") (pin "4") (pinfunction "COM_4") (pintype "passive"))
      (node (ref "U15") (pin "4") (pinfunction "COM_4") (pintype "passive"))
      (node (ref "U16") (pin "4") (pinfunction "COM_4") (pintype "passive"))
      (node (ref "U17") (pin "2") (pinfunction "GND_2") (pintype "passive"))
      (node (ref "U18") (pin "7") (pinfunction "GND_7") (pintype "passive"))
      (node (ref "U18") (pin "8") (pinfunction "GND_8") (pintype "passive"))
      (node (ref "U19") (pin "1") (pinfunction "GND/ADJ_1") (pintype "passive"))
      (node (ref "U8") (pin "4") (pinfunction "V-_4") (pintype "passive"))
      (node (ref "U9") (pin "4") (pinfunction "V-_4") (pintype "passive"))
    )
    (net (code "58") (name "Net-(L1-Pad1)") (class "Default")
      (node (ref "L1") (pin "1") (pinfunction "1_1") (pintype "passive"))
      (node (ref "U18") (pin "5") (pinfunction "SW_5") (pintype "passive"))
      (node (ref "U18") (pin "6") (pinfunction "SW_6") (pintype "passive"))
    )
    (net (code "59") (name "Net-(Q1-G)") (class "Default")
      (node (ref "Q1") (pin "1") (pinfunction "G_1") (pintype "passive"))
      (node (ref "R64") (pin "2") (pinfunction "2_2") (pintype "passive"))
      (node (ref "R65") (pin "2") (pinfunction "2_2") (pintype "passive"))
    )
    (net (code "60") (name "Net-(Q1-S)") (class "Default")
      (node (ref "C38") (pin "1") (pinfunction "1_1") (pintype "passive"))
      (node (ref "Q1") (pin "3") (pinfunction "S_3") (pintype "passive"))
      (node (ref "Q2") (pin "2") (pinfunction "D_2") (pintype "passive"))
      (node (ref "R65") (pin "1") (pinfunction "1_1") (pintype "passive"))
      (node (ref "U10") (pin "3") (pinfunction "3_3") (pintype "passive"))
      (node (ref "U16") (pin "6") (pinfunction "VS_6") (pintype "passive"))
    )
    (net (code "61") (name "Net-(Q2-G)") (class "Default")
      (node (ref "Q2") (pin "1") (pinfunction "G_1") (pintype "passive"))
      (node (ref "R63") (pin "2") (pinfunction "2_2") (pintype "passive"))
      (node (ref "R66") (pin "2") (pinfunction "2_2") (pintype "passive"))
    )
    (net (code "62") (name "Net-(Q3-G)") (class "Default")
      (node (ref "Q3") (pin "1") (pinfunction "G_1") (pintype "passive"))
      (node (ref "R62") (pin "2") (pinfunction "2_2") (pintype "passive"))
      (node (ref "R67") (pin "2") (pinfunction "2_2") (pintype "passive"))
    )
    (net (code "63") (name "Net-(Q3-S)") (class "Default")
      (node (ref "C37") (pin "1") (pinfunction "1_1") (pintype "passive"))
      (node (ref "Q3") (pin "3") (pinfunction "S_3") (pintype "passive"))
      (node (ref "Q4") (pin "2") (pinfunction "D_2") (pintype "passive"))
      (node (ref "R67") (pin "1") (pinfunction "1_1") (pintype "passive"))
      (node (ref "U10") (pin "2") (pinfunction "2_2") (pintype "passive"))
      (node (ref "U15") (pin "6") (pinfunction "VS_6") (pintype "passive"))
    )
    (net (code "64") (name "Net-(Q4-G)") (class "Default")
      (node (ref "Q4") (pin "1") (pinfunction "G_1") (pintype "passive"))
      (node (ref "R61") (pin "2") (pinfunction "2_2") (pintype "passive"))
      (node (ref "R68") (pin "2") (pinfunction "2_2") (pintype "passive"))
    )
    (net (code "65") (name "Net-(Q5-G)") (class "Default")
      (node (ref "Q5") (pin "1") (pinfunction "G_1") (pintype "passive"))
      (node (ref "R60") (pin "2") (pinfunction "2_2") (pintype "passive"))
      (node (ref "R69") (pin "2") (pinfunction "2_2") (pintype "passive"))
    )
    (net (code "66") (name "Net-(Q12-D)") (class "Default")
      (node (ref "C36") (pin "1") (pinfunction "1_1") (pintype "passive"))
      (node (ref "Q12") (pin "2") (pinfunction "D_2") (pintype "passive"))
      (node (ref "Q5") (pin "3") (pinfunction "S_3") (pintype "passive"))
      (node (ref "R69") (pin "1") (pinfunction "1_1") (pintype "passive"))
      (node (ref "U10") (pin "1") (pinfunction "1_1") (pintype "passive"))
      (node (ref "U14") (pin "6") (pinfunction "VS_6") (pintype "passive"))
    )
    (net (code "67") (name "Net-(Q12-G)") (class "Default")
      (node (ref "Q12") (pin "1") (pinfunction "G_1") (pintype "passive"))
      (node (ref "R59") (pin "2") (pinfunction "2_2") (pintype "passive"))
      (node (ref "R70") (pin "2") (pinfunction "2_2") (pintype "passive"))
    )
    (net (code "68") (name "Net-(U8-+INA)") (class "Default")
      (node (ref "C29") (pin "1") (pinfunction "1_1") (pintype "passive"))
      (node (ref "R22") (pin "2") (pinfunction "2_2") (pintype "passive"))
      (node (ref "R23") (pin "1") (pinfunction "1_1") (pintype "passive"))
      (node (ref "U8") (pin "3") (pinfunction "+INA_3") (pintype "passive"))
    )
    (net (code "69") (name "Net-(U8-+INB)") (class "Default")
      (node (ref "R43") (pin "1") (pinfunction "1_1") (pintype "passive"))
      (node (ref "R44") (pin "1") (pinfunction "1_1") (pintype "passive"))
      (node (ref "U8") (pin "5") (pinfunction "+INB_5") (pintype "passive"))
    )
    (net (code "70") (name "Net-(U8--INB)") (class "Default")
      (node (ref "C31") (pin "1") (pinfunction "1_1") (pintype "passive"))
      (node (ref "R36") (pin "2") (pinfunction "2_2") (pintype "passive"))
      (node (ref "R42") (pin "1") (pinfunction "1_1") (pintype "passive"))
      (node (ref "U8") (pin "6") (pinfunction "-INB_6") (pintype "passive"))
    )
    (net (code "71") (name "Net-(U9-+INA)") (class "Default")
      (node (ref "R47") (pin "2") (pinfunction "2_2") (pintype "passive"))
      (node (ref "R48") (pin "2") (pinfunction "2_2") (pintype "passive"))
      (node (ref "U9") (pin "3") (pinfunction "+INA_3") (pintype "passive"))
    )
    (net (code "72") (name "Net-(U9-+INB)") (class "Default")
      (node (ref "R52") (pin "1") (pinfunction "1_1") (pintype "passive"))
      (node (ref "R53") (pin "1") (pinfunction "1_1") (pintype "passive"))
      (node (ref "U9") (pin "5") (pinfunction "+INB_5") (pintype "passive"))
    )
    (net (code "73") (name "Net-(U9--INA)") (class "Default")
      (node (ref "C32") (pin "2") (pinfunction "2_2") (pintype "passive"))
      (node (ref "R49") (pin "1") (pinfunction "1_1") (pintype "passive"))
      (node (ref "R50") (pin "2") (pinfunction "2_2") (pintype "passive"))
      (node (ref "U9") (pin "2") (pinfunction "-INA_2") (pintype "passive"))
    )
    (net (code "74") (name "Net-(U9--INB)") (class "Default")
      (node (ref "C34") (pin "1") (pinfunction "1_1") (pintype "passive"))
      (node (ref "R54") (pin "1") (pinfunction "1_1") (pintype "passive"))
      (node (ref "R55") (pin "2") (pinfunction "2_2") (pintype "passive"))
      (node (ref "U9") (pin "6") (pinfunction "-INB_6") (pintype "passive"))
    )
    (net (code "75") (name "Net-(U14-HO)") (class "Default")
      (node (ref "R60") (pin "1") (pinfunction "1_1") (pintype "passive"))
      (node (ref "U14") (pin "7") (pinfunction "HO_7") (pintype "passive"))
    )
    (net (code "76") (name "Net-(U14-LO)") (class "Default")
      (node (ref "R59") (pin "1") (pinfunction "1_1") (pintype "passive"))
      (node (ref "U14") (pin "5") (pinfunction "LO_5") (pintype "passive"))
    )
    (net (code "77") (name "Net-(U14-VB)") (class "Default")
      (node (ref "C36") (pin "2") (pinfunction "2_2") (pintype "passive"))
      (node (ref "D1") (pin "1") (pinfunction "1_1") (pintype "passive"))
      (node (ref "U14") (pin "8") (pinfunction "VB_8") (pintype "passive"))
    )
    (net (code "78") (name "Net-(U15-HO)") (class "Default")
      (node (ref "R62") (pin "1") (pinfunction "1_1") (pintype "passive"))
      (node (ref "U15") (pin "7") (pinfunction "HO_7") (pintype "passive"))
    )
    (net (code "79") (name "Net-(U15-LO)") (class "Default")
      (node (ref "R61") (pin "1") (pinfunction "1_1") (pintype "passive"))
      (node (ref "U15") (pin "5") (pinfunction "LO_5") (pintype "passive"))
    )
    (net (code "80") (name "Net-(U15-VB)") (class "Default")
      (node (ref "C37") (pin "2") (pinfunction "2_2") (pintype "passive"))
      (node (ref "D2") (pin "1") (pinfunction "1_1") (pintype "passive"))
      (node (ref "U15") (pin "8") (pinfunction "VB_8") (pintype "passive"))
    )
    (net (code "81") (name "Net-(U16-HO)") (class "Default")
      (node (ref "R64") (pin "1") (pinfunction "1_1") (pintype "passive"))
      (node (ref "U16") (pin "7") (pinfunction "HO_7") (pintype "passive"))
    )
    (net (code "82") (name "Net-(U16-LO)") (class "Default")
      (node (ref "R63") (pin "1") (pinfunction "1_1") (pintype "passive"))
      (node (ref "U16") (pin "5") (pinfunction "LO_5") (pintype "passive"))
    )
    (net (code "83") (name "Net-(U16-VB)") (class "Default")
      (node (ref "C38") (pin "2") (pinfunction "2_2") (pintype "passive"))
      (node (ref "D3") (pin "1") (pinfunction "1_1") (pintype "passive"))
      (node (ref "U16") (pin "8") (pinfunction "VB_8") (pintype "passive"))
    )
    (net (code "84") (name "Net-(U18-FB)") (class "Default")
      (node (ref "C45") (pin "1") (pinfunction "1_1") (pintype "passive"))
      (node (ref "R71") (pin "1") (pinfunction "1_1") (pintype "passive"))
      (node (ref "R72") (pin "2") (pinfunction "2_2") (pintype "passive"))
      (node (ref "U18") (pin "1") (pinfunction "FB_1") (pintype "passive"))
    )
    (net (code "85") (name "Net-(U18-ILIM)") (class "Default")
      (node (ref "R73") (pin "2") (pinfunction "2_2") (pintype "passive"))
      (node (ref "U18") (pin "3") (pinfunction "ILIM_3") (pintype "passive"))
    )
    (net (code "86") (name "Net-(U18-RT)") (class "Default")
      (node (ref "R74") (pin "2") (pinfunction "2_2") (pintype "passive"))
      (node (ref "U18") (pin "2") (pinfunction "RT_2") (pintype "passive"))
    )
  )
)
